# Seeeduino_and_Temp.net
KiCad netlist of a schematic drawn in Altium Designer
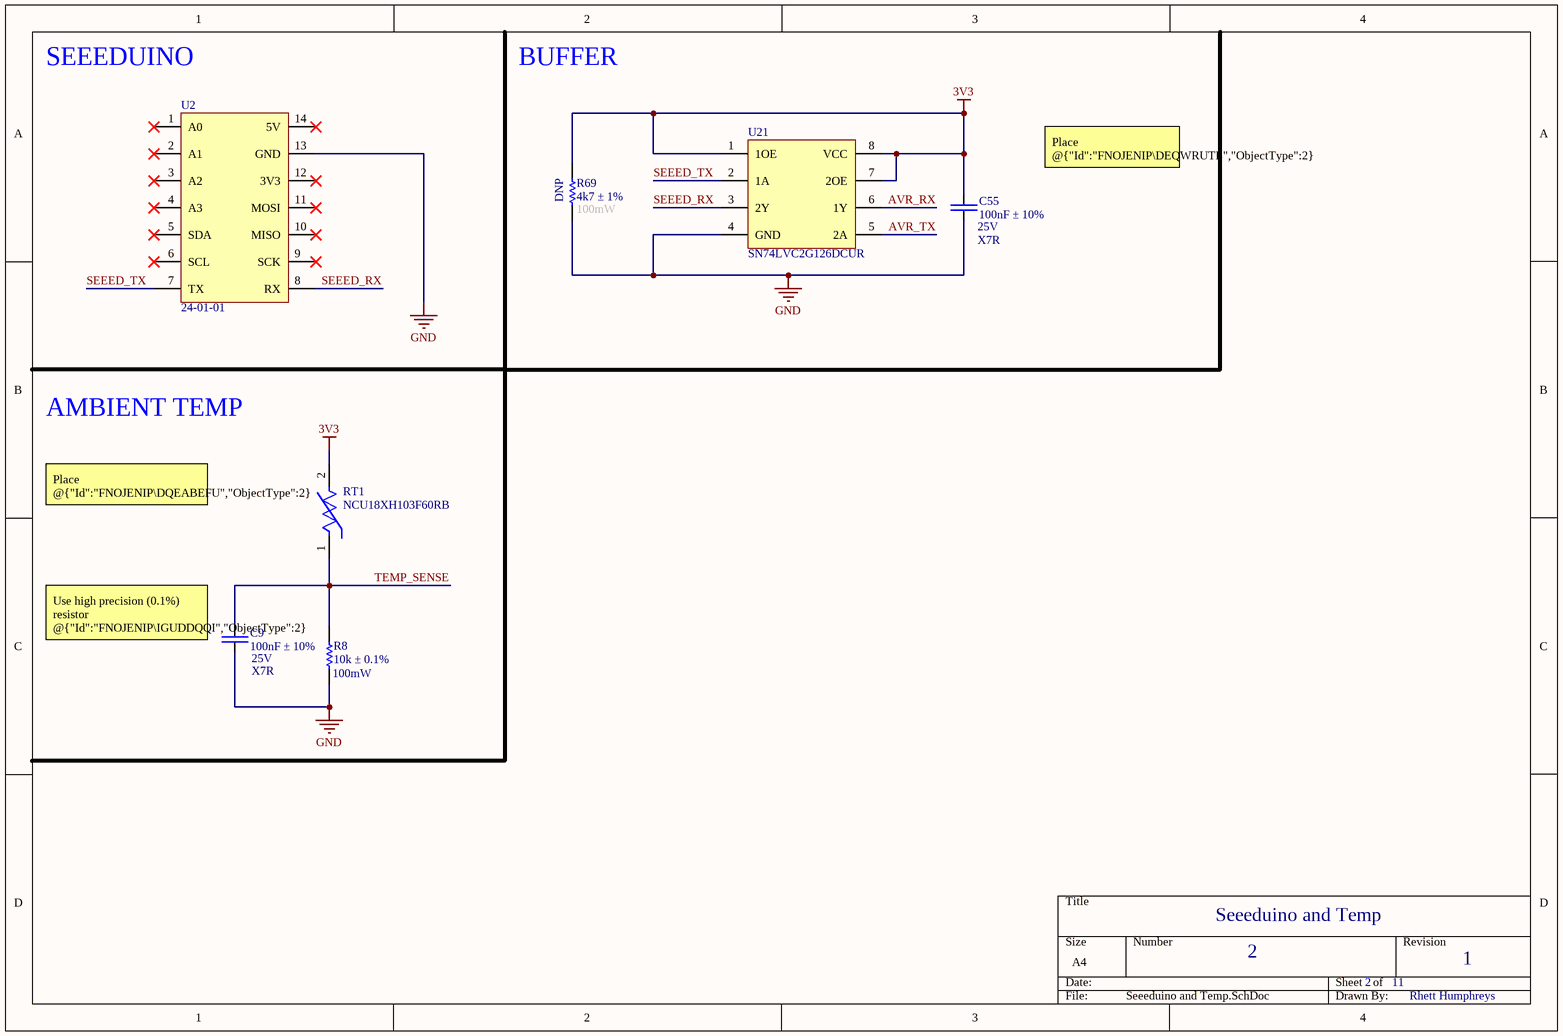
[diagram p0: Seeeduino and Temp.SchDoc]

(export (version "E")
  (design (tool "Eeschema 10.0.6"))
  (components
    (comp (ref "C9")
      (value "100nF ± 10%")
      (footprint "CAP-0603")
      (description "Capacitor chip unpolarized. 0603")
      (libsource (lib "Master") (part "CAP-0603"))
    )
    (comp (ref "C55")
      (value "100nF ± 10%")
      (footprint "CAP-0603")
      (description "Capacitor chip unpolarized. 0603")
      (libsource (lib "Master") (part "CAP-0603"))
    )
    (comp (ref "R8")
      (value "10k ± 0.1%")
      (footprint "RES-0603")
      (description "Resistor chip. 0603")
      (libsource (lib "Master") (part "RES-0603"))
    )
    (comp (ref "R69")
      (value "4k7 ± 1%")
      (footprint "RES-0603")
      (description "Resistor chip. 0603")
      (libsource (lib "Master") (part "RES-0603"))
    )
    (comp (ref "RT1")
      (value "NCU18XH103F60RB")
      (footprint "FP-NCU18-0_15-MFG")
      (description "THERMISTOR NTC")
      (libsource (lib "Altium Content Vault") (part "3b148a6ebabc5fb4d708a66c052d352"))
    )
    (comp (ref "U2")
      (value "24-01-01")
      (footprint "SEEEDUINO XIAO")
      (libsource (lib "Master") (part "SEEDUINO XIAO"))
    )
    (comp (ref "U21")
      (value "SN74LVC2G126DCUR")
      (footprint "TSSOP50P310X90-8N")
      (libsource (lib "Master") (part "SN74LVC2G126DCUR"))
    )
  )
  (nets
    (net (code "1") (name "/AVR_RX") (class "Default")
      (node (ref "U21") (pin "6") (pinfunction "1Y_6") (pintype "passive"))
    )
    (net (code "2") (name "/AVR_TX") (class "Default")
      (node (ref "U21") (pin "5") (pinfunction "2A_5") (pintype "passive"))
    )
    (net (code "3") (name "/SEEED_RX") (class "Default")
      (node (ref "U2") (pin "8") (pinfunction "RX_8") (pintype "passive"))
      (node (ref "U21") (pin "3") (pinfunction "2Y_3") (pintype "passive"))
    )
    (net (code "4") (name "/SEEED_TX") (class "Default")
      (node (ref "U2") (pin "7") (pinfunction "TX_7") (pintype "passive"))
      (node (ref "U21") (pin "2") (pinfunction "1A_2") (pintype "passive"))
    )
    (net (code "5") (name "/TEMP_SENSE") (class "Default")
      (node (ref "C9") (pin "2") (pintype "passive"))
      (node (ref "R8") (pin "1") (pintype "passive"))
      (node (ref "RT1") (pin "1") (pinfunction "1_1") (pintype "passive"))
    )
    (net (code "6") (name "3V3") (class "Default")
      (node (ref "C55") (pin "2") (pintype "passive"))
      (node (ref "R69") (pin "1") (pintype "passive"))
      (node (ref "RT1") (pin "2") (pinfunction "2_2") (pintype "passive"))
      (node (ref "U21") (pin "1") (pinfunction "1OE_1") (pintype "passive"))
      (node (ref "U21") (pin "7") (pinfunction "2OE_7") (pintype "passive"))
      (node (ref "U21") (pin "8") (pinfunction "VCC_8") (pintype "passive"))
    )
    (net (code "7") (name "GND") (class "Default")
      (node (ref "C55") (pin "1") (pintype "passive"))
      (node (ref "C9") (pin "1") (pintype "passive"))
      (node (ref "R69") (pin "2") (pintype "passive"))
      (node (ref "R8") (pin "2") (pintype "passive"))
      (node (ref "U2") (pin "13") (pinfunction "GND_13") (pintype "passive"))
      (node (ref "U21") (pin "4") (pinfunction "GND_4") (pintype "passive"))
    )
    (net (code "8") (name "unconnected-(U2-3V3-Pad12)") (class "Default")
      (node (ref "U2") (pin "12") (pinfunction "3V3_12") (pintype "passive+no_connect"))
    )
    (net (code "9") (name "unconnected-(U2-5V-Pad14)") (class "Default")
      (node (ref "U2") (pin "14") (pinfunction "5V_14") (pintype "passive+no_connect"))
    )
    (net (code "10") (name "unconnected-(U2-A0-Pad1)") (class "Default")
      (node (ref "U2") (pin "1") (pinfunction "A0_1") (pintype "passive+no_connect"))
    )
    (net (code "11") (name "unconnected-(U2-A1-Pad2)") (class "Default")
      (node (ref "U2") (pin "2") (pinfunction "A1_2") (pintype "passive+no_connect"))
    )
    (net (code "12") (name "unconnected-(U2-A2-Pad3)") (class "Default")
      (node (ref "U2") (pin "3") (pinfunction "A2_3") (pintype "passive+no_connect"))
    )
    (net (code "13") (name "unconnected-(U2-A3-Pad4)") (class "Default")
      (node (ref "U2") (pin "4") (pinfunction "A3_4") (pintype "passive+no_connect"))
    )
    (net (code "14") (name "unconnected-(U2-MISO-Pad10)") (class "Default")
      (node (ref "U2") (pin "10") (pinfunction "MISO_10") (pintype "passive+no_connect"))
    )
    (net (code "15") (name "unconnected-(U2-MOSI-Pad11)") (class "Default")
      (node (ref "U2") (pin "11") (pinfunction "MOSI_11") (pintype "passive+no_connect"))
    )
    (net (code "16") (name "unconnected-(U2-SCK-Pad9)") (class "Default")
      (node (ref "U2") (pin "9") (pinfunction "SCK_9") (pintype "passive+no_connect"))
    )
    (net (code "17") (name "unconnected-(U2-SCL-Pad6)") (class "Default")
      (node (ref "U2") (pin "6") (pinfunction "SCL_6") (pintype "passive+no_connect"))
    )
    (net (code "18") (name "unconnected-(U2-SDA-Pad5)") (class "Default")
      (node (ref "U2") (pin "5") (pinfunction "SDA_5") (pintype "passive+no_connect"))
    )
  )
)
